# Pure_Noise.net
KiCad netlist of a schematic drawn in EAGLE
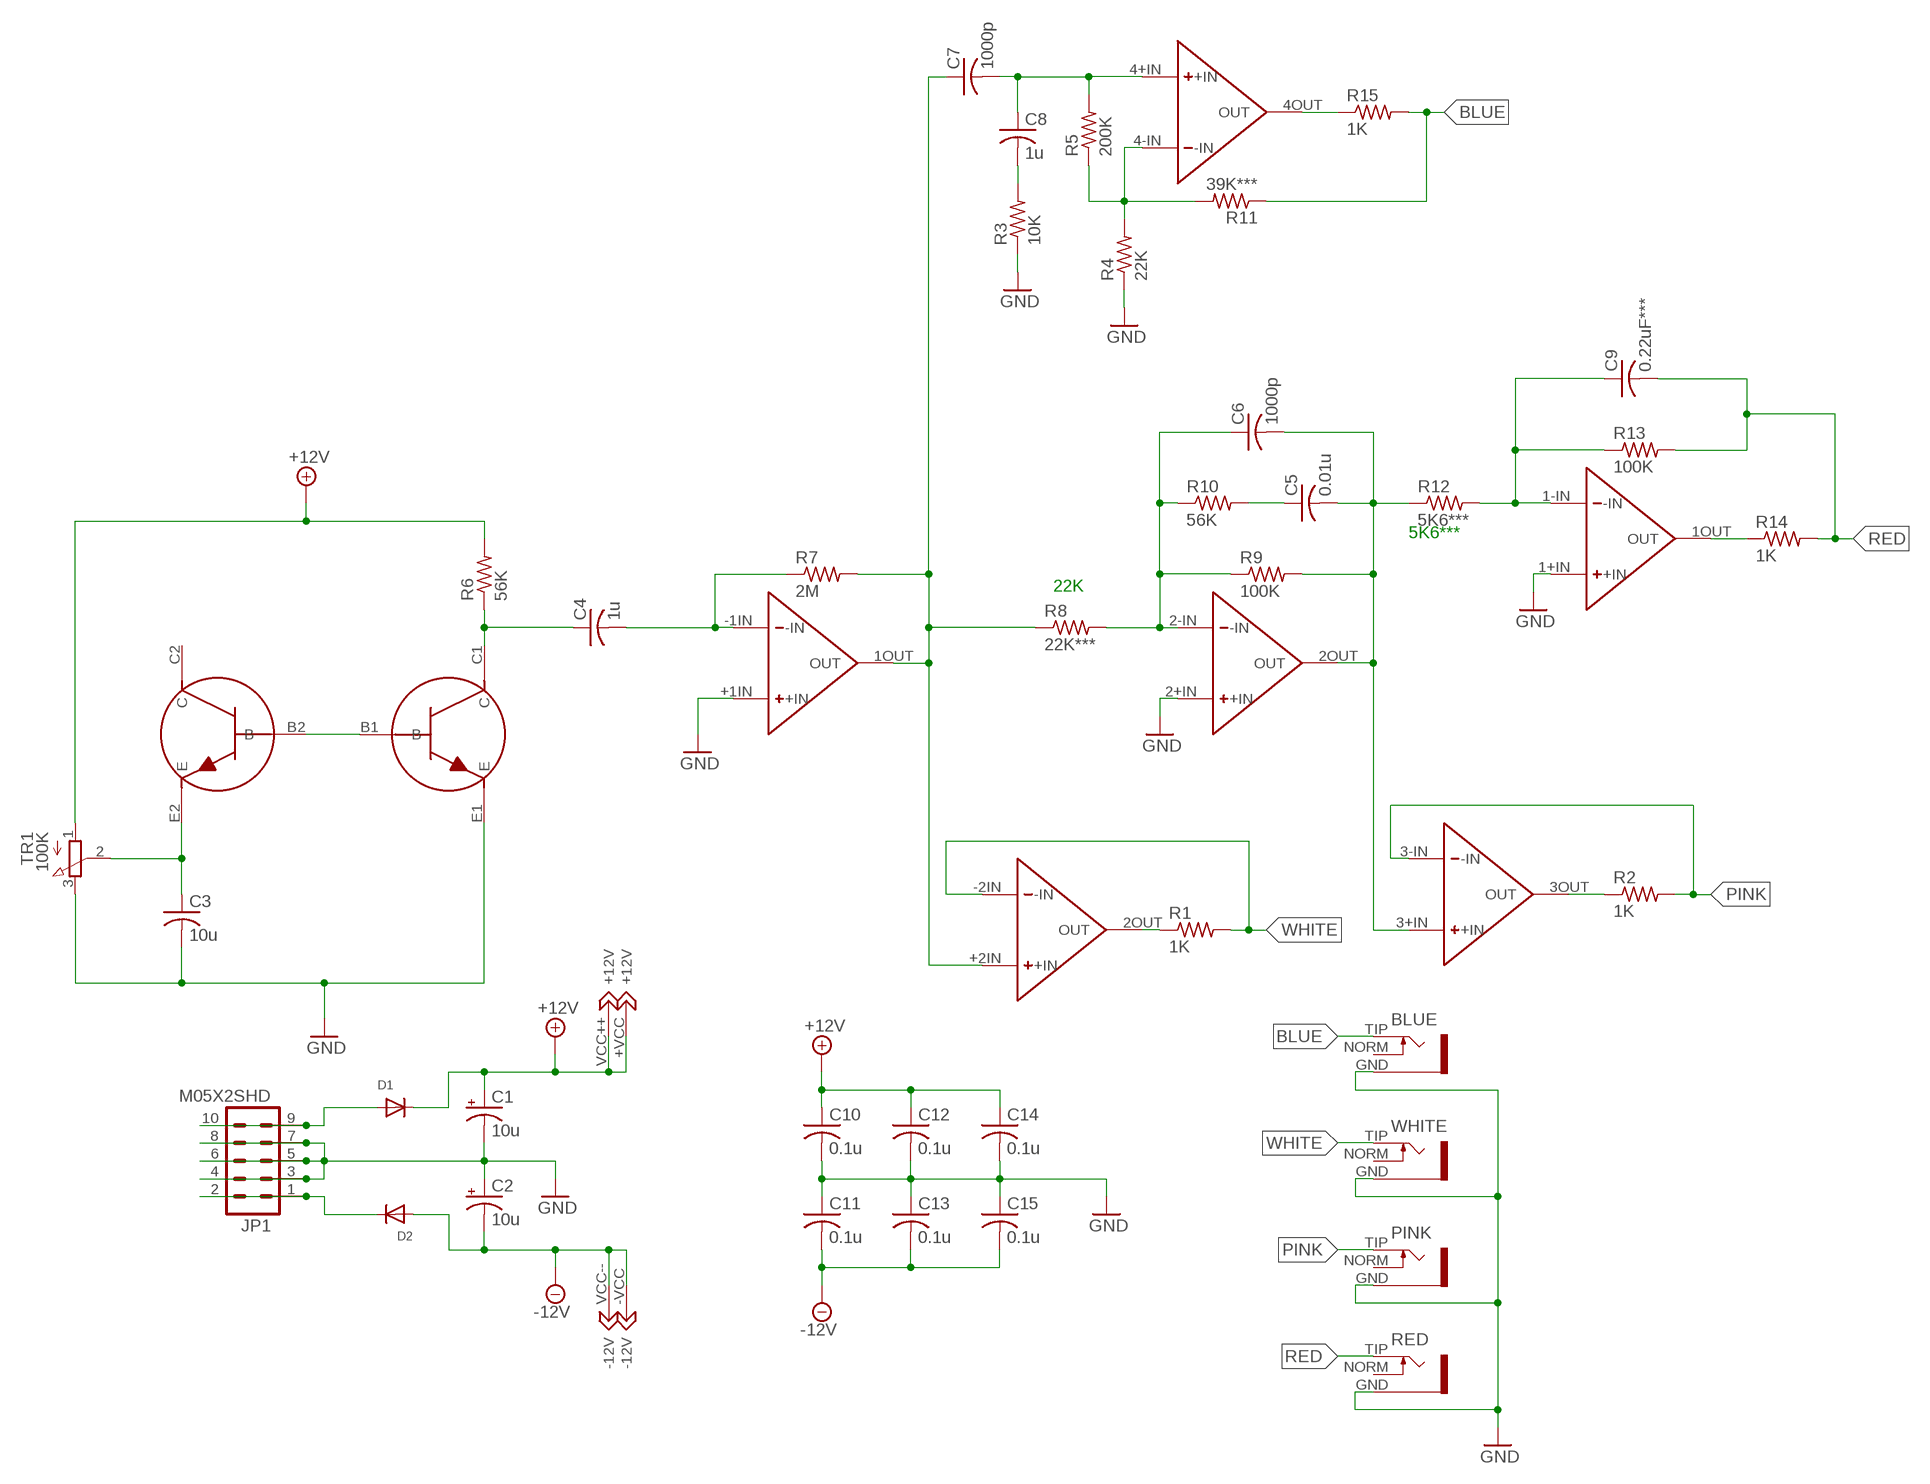
[diagram p0: schematic, sheet 1]

(export (version "E")
  (design (tool "Eeschema 10.0.6"))
  (components
    (comp (ref "BLUE")
      (value "S_JACK")
      (footprint "eagle-import:S_JACK")
      (libsource (lib "eagle-import") (part "S_JACK"))
    )
    (comp (ref "C1")
      (value "10u")
      (footprint "eagle-import:153CLV-0505")
      (libsource (lib "eagle-import") (part "CPOL-US153CLV-0505"))
    )
    (comp (ref "C2")
      (value "10u")
      (footprint "eagle-import:153CLV-0505")
      (libsource (lib "eagle-import") (part "CPOL-US153CLV-0505"))
    )
    (comp (ref "C3")
      (value "10u")
      (footprint "eagle-import:C1206K")
      (libsource (lib "eagle-import") (part "C-USC1206K"))
    )
    (comp (ref "C4")
      (value "1u")
      (footprint "eagle-import:C0805K")
      (libsource (lib "eagle-import") (part "C-USC0805K"))
    )
    (comp (ref "C5")
      (value "0.01u")
      (footprint "eagle-import:C0805K")
      (libsource (lib "eagle-import") (part "C-USC0805K"))
    )
    (comp (ref "C6")
      (value "1000p")
      (footprint "eagle-import:C0805K")
      (libsource (lib "eagle-import") (part "C-USC0805K"))
    )
    (comp (ref "C7")
      (value "1000p")
      (footprint "eagle-import:C0805K")
      (libsource (lib "eagle-import") (part "C-USC0805K"))
    )
    (comp (ref "C8")
      (value "1u")
      (footprint "eagle-import:C0805K")
      (libsource (lib "eagle-import") (part "C-USC0805K"))
    )
    (comp (ref "C9")
      (value "0.22uF***")
      (footprint "eagle-import:C0805K")
      (libsource (lib "eagle-import") (part "C-USC0805K"))
    )
    (comp (ref "C10")
      (value "0.1u")
      (footprint "eagle-import:C0805K")
      (libsource (lib "eagle-import") (part "C-USC0805K"))
    )
    (comp (ref "C11")
      (value "0.1u")
      (footprint "eagle-import:C0805K")
      (libsource (lib "eagle-import") (part "C-USC0805K"))
    )
    (comp (ref "C12")
      (value "0.1u")
      (footprint "eagle-import:C0805K")
      (libsource (lib "eagle-import") (part "C-USC0805K"))
    )
    (comp (ref "C13")
      (value "0.1u")
      (footprint "eagle-import:C0805K")
      (libsource (lib "eagle-import") (part "C-USC0805K"))
    )
    (comp (ref "C14")
      (value "0.1u")
      (footprint "eagle-import:C0805K")
      (libsource (lib "eagle-import") (part "C-USC0805K"))
    )
    (comp (ref "C15")
      (value "0.1u")
      (footprint "eagle-import:C0805K")
      (libsource (lib "eagle-import") (part "C-USC0805K"))
    )
    (comp (ref "D1")
      (value "DIODESMA")
      (footprint "eagle-import:SMADIODE")
      (libsource (lib "eagle-import") (part "DIODESMA"))
    )
    (comp (ref "D2")
      (value "DIODESMA")
      (footprint "eagle-import:SMADIODE")
      (libsource (lib "eagle-import") (part "DIODESMA"))
    )
    (comp (ref "JP1")
      (value "M05X2SHD")
      (footprint "eagle-import:2X5-SHROUDED")
      (libsource (lib "eagle-import") (part "M05X2SHD"))
    )
    (comp (ref "PINK")
      (value "S_JACK")
      (footprint "eagle-import:S_JACK")
      (libsource (lib "eagle-import") (part "S_JACK"))
    )
    (comp (ref "R1")
      (value "1K")
      (footprint "eagle-import:R0805")
      (libsource (lib "eagle-import") (part "R-US_R0805"))
    )
    (comp (ref "R2")
      (value "1K")
      (footprint "eagle-import:R0805")
      (libsource (lib "eagle-import") (part "R-US_R0805"))
    )
    (comp (ref "R3")
      (value "10K")
      (footprint "eagle-import:R0805")
      (libsource (lib "eagle-import") (part "R-US_R0805"))
    )
    (comp (ref "R4")
      (value "22K")
      (footprint "eagle-import:R0805")
      (libsource (lib "eagle-import") (part "R-US_R0805"))
    )
    (comp (ref "R5")
      (value "200K")
      (footprint "eagle-import:R0805")
      (libsource (lib "eagle-import") (part "R-US_R0805"))
    )
    (comp (ref "R6")
      (value "56K")
      (footprint "eagle-import:R0805")
      (libsource (lib "eagle-import") (part "R-US_R0805"))
    )
    (comp (ref "R7")
      (value "2M")
      (footprint "eagle-import:R0805")
      (libsource (lib "eagle-import") (part "R-US_R0805"))
    )
    (comp (ref "R8")
      (value "22K***")
      (footprint "eagle-import:R0805")
      (libsource (lib "eagle-import") (part "R-US_R0805"))
    )
    (comp (ref "R9")
      (value "100K")
      (footprint "eagle-import:R0805")
      (libsource (lib "eagle-import") (part "R-US_R0805"))
    )
    (comp (ref "R10")
      (value "56K")
      (footprint "eagle-import:R0805")
      (libsource (lib "eagle-import") (part "R-US_R0805"))
    )
    (comp (ref "R11")
      (value "39K***")
      (footprint "eagle-import:R0805")
      (libsource (lib "eagle-import") (part "R-US_R0805"))
    )
    (comp (ref "R12")
      (value "5K6***")
      (footprint "eagle-import:R0805")
      (libsource (lib "eagle-import") (part "R-US_R0805"))
    )
    (comp (ref "R13")
      (value "100K")
      (footprint "eagle-import:R0805")
      (libsource (lib "eagle-import") (part "R-US_R0805"))
    )
    (comp (ref "R14")
      (value "1K")
      (footprint "eagle-import:R0805")
      (libsource (lib "eagle-import") (part "R-US_R0805"))
    )
    (comp (ref "R15")
      (value "1K")
      (footprint "eagle-import:R0805")
      (libsource (lib "eagle-import") (part "R-US_R0805"))
    )
    (comp (ref "RED")
      (value "S_JACK")
      (footprint "eagle-import:S_JACK")
      (libsource (lib "eagle-import") (part "S_JACK"))
    )
    (comp (ref "TR1")
      (value "100K")
      (footprint "eagle-import:TRIMMER_TH3")
      (libsource (lib "eagle-import") (part "TRIMMER_TH3"))
    )
    (comp (ref "U$1")
      (value "DUAL_OPAMP")
      (footprint "eagle-import:DUAL_OPAMP")
      (libsource (lib "eagle-import") (part "DUAL_OPAMP"))
    )
    (comp (ref "U$6")
      (value "QUAD_OPAMP")
      (footprint "eagle-import:QUAD_OPAMP")
      (libsource (lib "eagle-import") (part "QUAD_OPAMP"))
    )
    (comp (ref "U$9")
      (value "TRANS_PAIR")
      (footprint "eagle-import:TRANS_PAIR")
      (libsource (lib "eagle-import") (part "TRANS_PAIR"))
    )
    (comp (ref "WHITE")
      (value "S_JACK")
      (footprint "eagle-import:S_JACK")
      (libsource (lib "eagle-import") (part "S_JACK"))
    )
  )
  (nets
    (net (code "1") (name "+12V") (class "Default")
      (node (ref "C1") (pin "+") (pinfunction "+_+") (pintype "passive"))
      (node (ref "C10") (pin "1") (pinfunction "1_1") (pintype "passive"))
      (node (ref "C12") (pin "1") (pinfunction "1_1") (pintype "passive"))
      (node (ref "C14") (pin "1") (pinfunction "1_1") (pintype "passive"))
      (node (ref "D1") (pin "C") (pinfunction "C_C") (pintype "passive"))
      (node (ref "R6") (pin "2") (pinfunction "2_2") (pintype "passive"))
      (node (ref "TR1") (pin "1") (pinfunction "1_1") (pintype "passive"))
      (node (ref "U$1") (pin "+VCC") (pinfunction "+12V_+VCC") (pintype "bidirectional"))
      (node (ref "U$6") (pin "VCC++") (pinfunction "+12V_VCC++") (pintype "bidirectional"))
    )
    (net (code "2") (name "-12V") (class "Default")
      (node (ref "C11") (pin "2") (pinfunction "2_2") (pintype "passive"))
      (node (ref "C13") (pin "2") (pinfunction "2_2") (pintype "passive"))
      (node (ref "C15") (pin "2") (pinfunction "2_2") (pintype "passive"))
      (node (ref "C2") (pin "-") (pinfunction "-_-") (pintype "passive"))
      (node (ref "D2") (pin "A") (pinfunction "A_A") (pintype "passive"))
      (node (ref "U$1") (pin "-VCC") (pinfunction "-12V_-VCC") (pintype "bidirectional"))
      (node (ref "U$6") (pin "VCC--") (pinfunction "-12V_VCC--") (pintype "bidirectional"))
    )
    (net (code "3") (name "BLUE") (class "Default")
      (node (ref "BLUE") (pin "TIP") (pinfunction "TIP_TIP") (pintype "passive"))
      (node (ref "R11") (pin "1") (pinfunction "1_1") (pintype "passive"))
      (node (ref "R15") (pin "2") (pinfunction "2_2") (pintype "passive"))
    )
    (net (code "4") (name "GND") (class "Default")
      (node (ref "BLUE") (pin "GND") (pinfunction "GND_GND") (pintype "passive"))
      (node (ref "C1") (pin "-") (pinfunction "-_-") (pintype "passive"))
      (node (ref "C10") (pin "2") (pinfunction "2_2") (pintype "passive"))
      (node (ref "C11") (pin "1") (pinfunction "1_1") (pintype "passive"))
      (node (ref "C12") (pin "2") (pinfunction "2_2") (pintype "passive"))
      (node (ref "C13") (pin "1") (pinfunction "1_1") (pintype "passive"))
      (node (ref "C14") (pin "2") (pinfunction "2_2") (pintype "passive"))
      (node (ref "C15") (pin "1") (pinfunction "1_1") (pintype "passive"))
      (node (ref "C2") (pin "+") (pinfunction "+_+") (pintype "passive"))
      (node (ref "C3") (pin "2") (pinfunction "2_2") (pintype "passive"))
      (node (ref "JP1") (pin "3") (pinfunction "3_3") (pintype "passive"))
      (node (ref "JP1") (pin "4") (pinfunction "4_4") (pintype "passive"))
      (node (ref "JP1") (pin "5") (pinfunction "5_5") (pintype "passive"))
      (node (ref "JP1") (pin "6") (pinfunction "6_6") (pintype "passive"))
      (node (ref "JP1") (pin "7") (pinfunction "7_7") (pintype "passive"))
      (node (ref "JP1") (pin "8") (pinfunction "8_8") (pintype "passive"))
      (node (ref "PINK") (pin "GND") (pinfunction "GND_GND") (pintype "passive"))
      (node (ref "R3") (pin "1") (pinfunction "1_1") (pintype "passive"))
      (node (ref "R4") (pin "1") (pinfunction "1_1") (pintype "passive"))
      (node (ref "RED") (pin "GND") (pinfunction "GND_GND") (pintype "passive"))
      (node (ref "TR1") (pin "3") (pinfunction "3_3") (pintype "passive"))
      (node (ref "U$1") (pin "+1IN") (pinfunction "+IN_+1IN") (pintype "bidirectional"))
      (node (ref "U$6") (pin "1+IN") (pinfunction "+IN_1+IN") (pintype "bidirectional"))
      (node (ref "U$6") (pin "2+IN") (pinfunction "+IN_2+IN") (pintype "bidirectional"))
      (node (ref "U$9") (pin "E1") (pinfunction "E_E1") (pintype "bidirectional"))
      (node (ref "WHITE") (pin "GND") (pinfunction "GND_GND") (pintype "passive"))
    )
    (net (code "5") (name "Net-(C5-Pad1)") (class "Default")
      (node (ref "C5") (pin "1") (pinfunction "1_1") (pintype "passive"))
      (node (ref "R10") (pin "2") (pinfunction "2_2") (pintype "passive"))
    )
    (net (code "6") (name "Net-(C8-Pad2)") (class "Default")
      (node (ref "C8") (pin "2") (pinfunction "2_2") (pintype "passive"))
      (node (ref "R3") (pin "2") (pinfunction "2_2") (pintype "passive"))
    )
    (net (code "7") (name "Net-(D1-PadA)") (class "Default")
      (node (ref "D1") (pin "A") (pinfunction "A_A") (pintype "passive"))
      (node (ref "JP1") (pin "10") (pinfunction "10_10") (pintype "passive"))
      (node (ref "JP1") (pin "9") (pinfunction "9_9") (pintype "passive"))
    )
    (net (code "8") (name "Net-(D2-PadC)") (class "Default")
      (node (ref "D2") (pin "C") (pinfunction "C_C") (pintype "passive"))
      (node (ref "JP1") (pin "1") (pinfunction "1_1") (pintype "passive"))
      (node (ref "JP1") (pin "2") (pinfunction "2_2") (pintype "passive"))
    )
    (net (code "9") (name "Net-(U$1A--IN)") (class "Default")
      (node (ref "C4") (pin "2") (pinfunction "2_2") (pintype "passive"))
      (node (ref "R7") (pin "1") (pinfunction "1_1") (pintype "passive"))
      (node (ref "U$1") (pin "-1IN") (pinfunction "-IN_-1IN") (pintype "bidirectional"))
    )
    (net (code "10") (name "Net-(U$1A-OUT)") (class "Default")
      (node (ref "C7") (pin "1") (pinfunction "1_1") (pintype "passive"))
      (node (ref "R7") (pin "2") (pinfunction "2_2") (pintype "passive"))
      (node (ref "R8") (pin "1") (pinfunction "1_1") (pintype "passive"))
      (node (ref "U$1") (pin "+2IN") (pinfunction "+IN_+2IN") (pintype "bidirectional"))
      (node (ref "U$1") (pin "1OUT") (pinfunction "OUT_1OUT") (pintype "bidirectional"))
    )
    (net (code "11") (name "Net-(U$1B-OUT)") (class "Default")
      (node (ref "R1") (pin "1") (pinfunction "1_1") (pintype "passive"))
      (node (ref "U$1") (pin "2OUT") (pinfunction "OUT_2OUT") (pintype "bidirectional"))
    )
    (net (code "12") (name "Net-(U$6A--IN)") (class "Default")
      (node (ref "C9") (pin "1") (pinfunction "1_1") (pintype "passive"))
      (node (ref "R12") (pin "2") (pinfunction "2_2") (pintype "passive"))
      (node (ref "R13") (pin "1") (pinfunction "1_1") (pintype "passive"))
      (node (ref "U$6") (pin "1-IN") (pinfunction "-IN_1-IN") (pintype "bidirectional"))
    )
    (net (code "13") (name "Net-(U$6A-OUT)") (class "Default")
      (node (ref "R14") (pin "1") (pinfunction "1_1") (pintype "passive"))
      (node (ref "U$6") (pin "1OUT") (pinfunction "OUT_1OUT") (pintype "bidirectional"))
    )
    (net (code "14") (name "Net-(U$6B--IN)") (class "Default")
      (node (ref "C6") (pin "1") (pinfunction "1_1") (pintype "passive"))
      (node (ref "R10") (pin "1") (pinfunction "1_1") (pintype "passive"))
      (node (ref "R8") (pin "2") (pinfunction "2_2") (pintype "passive"))
      (node (ref "R9") (pin "1") (pinfunction "1_1") (pintype "passive"))
      (node (ref "U$6") (pin "2-IN") (pinfunction "-IN_2-IN") (pintype "bidirectional"))
    )
    (net (code "15") (name "Net-(U$6B-OUT)") (class "Default")
      (node (ref "C5") (pin "2") (pinfunction "2_2") (pintype "passive"))
      (node (ref "C6") (pin "2") (pinfunction "2_2") (pintype "passive"))
      (node (ref "R12") (pin "1") (pinfunction "1_1") (pintype "passive"))
      (node (ref "R9") (pin "2") (pinfunction "2_2") (pintype "passive"))
      (node (ref "U$6") (pin "2OUT") (pinfunction "OUT_2OUT") (pintype "bidirectional"))
      (node (ref "U$6") (pin "3+IN") (pinfunction "+IN_3+IN") (pintype "bidirectional"))
    )
    (net (code "16") (name "Net-(U$6C-OUT)") (class "Default")
      (node (ref "R2") (pin "1") (pinfunction "1_1") (pintype "passive"))
      (node (ref "U$6") (pin "3OUT") (pinfunction "OUT_3OUT") (pintype "bidirectional"))
    )
    (net (code "17") (name "Net-(U$6D-+IN)") (class "Default")
      (node (ref "C7") (pin "2") (pinfunction "2_2") (pintype "passive"))
      (node (ref "C8") (pin "1") (pinfunction "1_1") (pintype "passive"))
      (node (ref "R5") (pin "2") (pinfunction "2_2") (pintype "passive"))
      (node (ref "U$6") (pin "4+IN") (pinfunction "+IN_4+IN") (pintype "bidirectional"))
    )
    (net (code "18") (name "Net-(U$6D--IN)") (class "Default")
      (node (ref "R11") (pin "2") (pinfunction "2_2") (pintype "passive"))
      (node (ref "R4") (pin "2") (pinfunction "2_2") (pintype "passive"))
      (node (ref "R5") (pin "1") (pinfunction "1_1") (pintype "passive"))
      (node (ref "U$6") (pin "4-IN") (pinfunction "-IN_4-IN") (pintype "bidirectional"))
    )
    (net (code "19") (name "Net-(U$6D-OUT)") (class "Default")
      (node (ref "R15") (pin "1") (pinfunction "1_1") (pintype "passive"))
      (node (ref "U$6") (pin "4OUT") (pinfunction "OUT_4OUT") (pintype "bidirectional"))
    )
    (net (code "20") (name "Net-(U$9A-B)") (class "Default")
      (node (ref "U$9") (pin "B1") (pinfunction "B_B1") (pintype "bidirectional"))
      (node (ref "U$9") (pin "B2") (pinfunction "B_B2") (pintype "bidirectional"))
    )
    (net (code "21") (name "Net-(U$9A-C)") (class "Default")
      (node (ref "C4") (pin "1") (pinfunction "1_1") (pintype "passive"))
      (node (ref "R6") (pin "1") (pinfunction "1_1") (pintype "passive"))
      (node (ref "U$9") (pin "C1") (pinfunction "C_C1") (pintype "bidirectional"))
    )
    (net (code "22") (name "Net-(U$9B-E)") (class "Default")
      (node (ref "C3") (pin "1") (pinfunction "1_1") (pintype "passive"))
      (node (ref "TR1") (pin "2") (pinfunction "2_2") (pintype "passive"))
      (node (ref "U$9") (pin "E2") (pinfunction "E_E2") (pintype "bidirectional"))
    )
    (net (code "23") (name "PINK") (class "Default")
      (node (ref "PINK") (pin "TIP") (pinfunction "TIP_TIP") (pintype "passive"))
      (node (ref "R2") (pin "2") (pinfunction "2_2") (pintype "passive"))
      (node (ref "U$6") (pin "3-IN") (pinfunction "-IN_3-IN") (pintype "bidirectional"))
    )
    (net (code "24") (name "RED") (class "Default")
      (node (ref "C9") (pin "2") (pinfunction "2_2") (pintype "passive"))
      (node (ref "R13") (pin "2") (pinfunction "2_2") (pintype "passive"))
      (node (ref "R14") (pin "2") (pinfunction "2_2") (pintype "passive"))
      (node (ref "RED") (pin "TIP") (pinfunction "TIP_TIP") (pintype "passive"))
    )
    (net (code "25") (name "WHITE") (class "Default")
      (node (ref "R1") (pin "2") (pinfunction "2_2") (pintype "passive"))
      (node (ref "U$1") (pin "-2IN") (pinfunction "-IN_-2IN") (pintype "bidirectional"))
      (node (ref "WHITE") (pin "TIP") (pinfunction "TIP_TIP") (pintype "passive"))
    )
    (net (code "26") (name "unconnected-(BLUE-PadNORM)") (class "Default")
      (node (ref "BLUE") (pin "NORM") (pinfunction "NORM_NORM") (pintype "passive"))
    )
    (net (code "27") (name "unconnected-(PINK-PadNORM)") (class "Default")
      (node (ref "PINK") (pin "NORM") (pinfunction "NORM_NORM") (pintype "passive"))
    )
    (net (code "28") (name "unconnected-(RED-PadNORM)") (class "Default")
      (node (ref "RED") (pin "NORM") (pinfunction "NORM_NORM") (pintype "passive"))
    )
    (net (code "29") (name "unconnected-(U$9B-C-PadC2)") (class "Default")
      (node (ref "U$9") (pin "C2") (pinfunction "C_C2") (pintype "bidirectional"))
    )
    (net (code "30") (name "unconnected-(WHITE-PadNORM)") (class "Default")
      (node (ref "WHITE") (pin "NORM") (pinfunction "NORM_NORM") (pintype "passive"))
    )
  )
)
